# Sheet1.net
KiCad netlist of a schematic drawn in Altium Designer
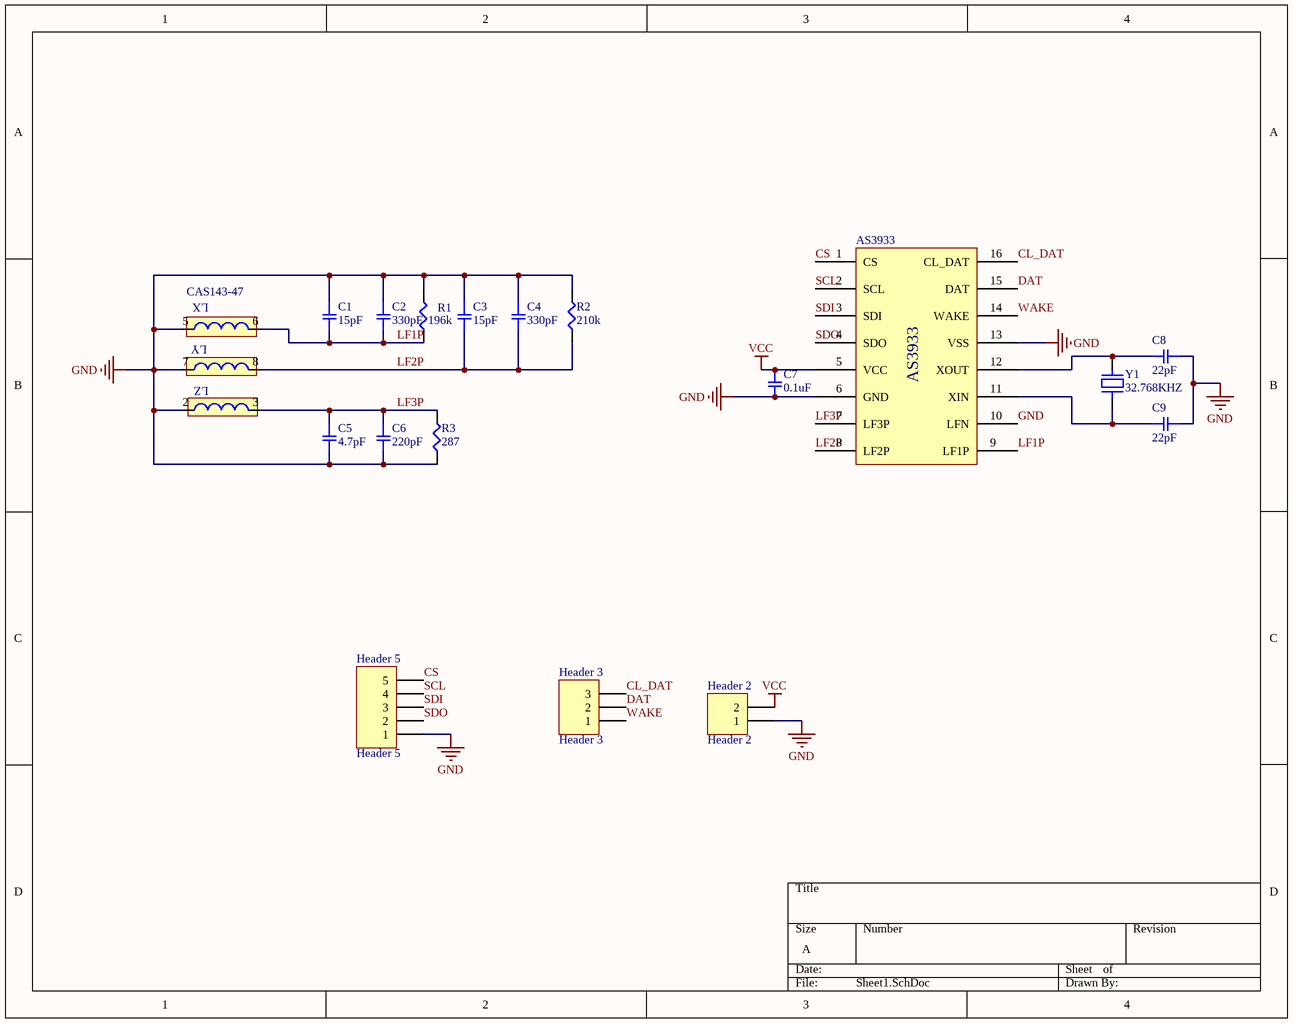
[diagram p0: Sheet1.SchDoc]

(export (version "E")
  (design (tool "Eeschema 10.0.6"))
  (components
    (comp (ref "AS3933")
      (value "~")
      (footprint "TSOP65P640X110-16N")
      (libsource (lib "AS3933") (part "Component_1"))
    )
    (comp (ref "C1")
      (value "15pF")
      (footprint "SMD-0805C")
      (description "Cap Ceramic 15pF 50V C0G 1%  0805")
      (fields (field (name "PART NUMBER") "CC0805FRNPO9BN150") (field (name "MANUFACTURER") "Yaego"))
      (libsource (lib "capacitor_0805") (part "CC0805FRNPO9BN150"))
    )
    (comp (ref "C2")
      (value "330pF")
      (footprint "SMD-0805C")
      (description "Cap Ceramic 330pF 50V C0G 2%  0805")
      (fields (field (name "PART NUMBER") "CC0805GRNPO9BN331") (field (name "MANUFACTURER") "Yageo"))
      (libsource (lib "capacitor_0805") (part "CC0805GRNPO9BN331"))
    )
    (comp (ref "C3")
      (value "15pF")
      (footprint "SMD-0805C")
      (description "Cap Ceramic 15pF 50V C0G 1%  0805")
      (fields (field (name "PART NUMBER") "CC0805FRNPO9BN150") (field (name "MANUFACTURER") "Yaego"))
      (libsource (lib "capacitor_0805") (part "CC0805FRNPO9BN150"))
    )
    (comp (ref "C4")
      (value "330pF")
      (footprint "SMD-0805C")
      (description "Cap Ceramic 330pF 50V C0G 2%  0805")
      (fields (field (name "PART NUMBER") "CC0805GRNPO9BN331") (field (name "MANUFACTURER") "Yageo"))
      (libsource (lib "capacitor_0805") (part "CC0805GRNPO9BN331"))
    )
    (comp (ref "C5")
      (value "4.7pF")
      (footprint "SMD-0805C")
      (description "Cap Ceramic 4.7pF 50V C0G 0.1pF  0805")
      (fields
        (field (name "PART NUMBER") "CL21C4R7BBANNNC")
        (field (name "MANUFACTURER") "Samsung Electro-Mechanics")
      )
      (libsource (lib "capacitor_0805") (part "CL21C4R7BBANNNC"))
    )
    (comp (ref "C6")
      (value "220pF")
      (footprint "SMD-0805C")
      (description "Cap Ceramic 220pF 100V C0G 1% 0805")
      (fields
        (field (name "PART NUMBER") "GCM2165C2A221FA16D")
        (field (name "MANUFACTURER") "Murata Manufacturing")
      )
      (libsource (lib "capacitor_0805") (part "GCM2165C2A221FA16D"))
    )
    (comp (ref "C7")
      (value "0.1uF")
      (footprint "SMD-0805C")
      (description "CAP CER 0.1uF 50V X7T 0805")
      (fields
        (field (name "PART NUMBER") "GC321AD72E103KX01D")
        (field (name "MANUFACTURER") "Samsung Electro-Mechanics")
      )
      (libsource (lib "capacitor_0805") (part "CL21B104JBCNNNC"))
    )
    (comp (ref "C8")
      (value "22pF")
      (footprint "SMD-0805C")
      (description "Cap Ceramic 22pF 50V C0G 5%0805")
      (fields
        (field (name "PART NUMBER") "CL21C220JBANNND")
        (field (name "MANUFACTURER") "Samsung Electro-Mechanics")
      )
      (libsource (lib "capacitor_0805") (part "CL21C220JBANNND"))
    )
    (comp (ref "C9")
      (value "22pF")
      (footprint "SMD-0805C")
      (description "Cap Ceramic 22pF 50V C0G 5%0805")
      (fields
        (field (name "PART NUMBER") "CL21C220JBANNND")
        (field (name "MANUFACTURER") "Samsung Electro-Mechanics")
      )
      (libsource (lib "capacitor_0805") (part "CL21C220JBANNND"))
    )
    (comp (ref "CAS143-47")
      (value "CAS143-47")
      (footprint "CAS143-47")
      (libsource (lib "CAS143-47") (part "Component_1"))
    )
    (comp (ref "Header 2")
      (value "Header 2")
      (footprint "HDR1X2")
      (description "Header, 2-Pin")
      (fields (field (name "PUBLISHER") "Altium Limited"))
      (libsource (lib "Miscellaneous Connectors") (part "Header 2"))
    )
    (comp (ref "Header 3")
      (value "Header 3")
      (footprint "HDR1X3")
      (description "Header, 3-Pin")
      (fields (field (name "PUBLISHER") "Altium Limited"))
      (libsource (lib "Miscellaneous Connectors") (part "Header 3"))
    )
    (comp (ref "Header 5")
      (value "Header 5")
      (footprint "HDR1X5")
      (description "Header, 5-Pin")
      (fields (field (name "PUBLISHER") "Altium Limited"))
      (libsource (lib "Miscellaneous Connectors") (part "Header 5"))
    )
    (comp (ref "R1")
      (value "196k")
      (footprint "SMD-0805-RES")
      (description "RES SMD 196K OHM 1% 1/8W 0805")
      (fields
        (field (name "PART NUMBER") "ERJ-6ENF1963V")
        (field (name "DIGI-KEY PART NUMBER") "P196KCCT-ND")
      )
      (libsource (lib "Panasonic_ERJ_0805") (part "ERJ-6ENF1963V"))
    )
    (comp (ref "R2")
      (value "210k")
      (footprint "SMD-0805-RES")
      (description "RES SMD 210K OHM 1% 1/8W 0805")
      (fields
        (field (name "PART NUMBER") "ERJ-6ENF2103V")
        (field (name "DIGI-KEY PART NUMBER") "P210KCCT-ND")
      )
      (libsource (lib "Panasonic_ERJ_0805") (part "ERJ-6ENF2103V"))
    )
    (comp (ref "R3")
      (value "287")
      (footprint "SMD-0805-RES")
      (description "RES SMD 287 OHM 1% 1/8W 0805")
      (fields (field (name "PART NUMBER") "ERJ-6ENF2870V") (field (name "DIGI-KEY PART NUMBER") "P287CCT-ND"))
      (libsource (lib "Panasonic_ERJ_0805") (part "ERJ-6ENF2870V"))
    )
    (comp (ref "Y1")
      (value "32.768KHZ")
      (footprint "ABRACON ABS07")
      (description "SMT Crystal")
      (libsource (lib "Crystals") (part "Abracon Crystal ABS07"))
    )
  )
  (nets
    (net (code "1") (name "/CL_DAT") (class "Default")
      (node (ref "AS3933") (pin "16") (pinfunction "CL_DAT_16") (pintype "passive"))
      (node (ref "Header 3") (pin "3") (pinfunction "3_3") (pintype "passive"))
    )
    (net (code "2") (name "/CS") (class "Default")
      (node (ref "AS3933") (pin "1") (pinfunction "CS_1") (pintype "passive"))
      (node (ref "Header 5") (pin "5") (pinfunction "5_5") (pintype "passive"))
    )
    (net (code "3") (name "/DAT") (class "Default")
      (node (ref "AS3933") (pin "15") (pinfunction "DAT_15") (pintype "passive"))
      (node (ref "Header 3") (pin "2") (pinfunction "2_2") (pintype "passive"))
    )
    (net (code "4") (name "/LF1P") (class "Default")
      (node (ref "AS3933") (pin "9") (pinfunction "LF1P_9") (pintype "passive"))
      (node (ref "C1") (pin "2") (pinfunction "2_2") (pintype "passive"))
      (node (ref "C2") (pin "2") (pinfunction "2_2") (pintype "passive"))
      (node (ref "CAS143-47") (pin "6") (pinfunction "6_6") (pintype "passive"))
      (node (ref "R1") (pin "1") (pinfunction "1_1") (pintype "passive"))
    )
    (net (code "5") (name "/LF2P") (class "Default")
      (node (ref "AS3933") (pin "8") (pinfunction "LF2P_8") (pintype "passive"))
      (node (ref "C3") (pin "2") (pinfunction "2_2") (pintype "passive"))
      (node (ref "C4") (pin "2") (pinfunction "2_2") (pintype "passive"))
      (node (ref "CAS143-47") (pin "8") (pinfunction "8_8") (pintype "passive"))
      (node (ref "R2") (pin "1") (pinfunction "1_1") (pintype "passive"))
    )
    (net (code "6") (name "/LF3P") (class "Default")
      (node (ref "AS3933") (pin "7") (pinfunction "LF3P_7") (pintype "passive"))
      (node (ref "C5") (pin "1") (pinfunction "1_1") (pintype "passive"))
      (node (ref "C6") (pin "1") (pinfunction "1_1") (pintype "passive"))
      (node (ref "CAS143-47") (pin "3") (pinfunction "3_3") (pintype "passive"))
      (node (ref "R3") (pin "2") (pinfunction "2_2") (pintype "passive"))
    )
    (net (code "7") (name "/SCL") (class "Default")
      (node (ref "AS3933") (pin "2") (pinfunction "SCL_2") (pintype "passive"))
      (node (ref "Header 5") (pin "4") (pinfunction "4_4") (pintype "passive"))
    )
    (net (code "8") (name "/SDI") (class "Default")
      (node (ref "AS3933") (pin "3") (pinfunction "SDI_3") (pintype "passive"))
      (node (ref "Header 5") (pin "3") (pinfunction "3_3") (pintype "passive"))
    )
    (net (code "9") (name "/SDO") (class "Default")
      (node (ref "AS3933") (pin "4") (pinfunction "SDO_4") (pintype "passive"))
      (node (ref "Header 5") (pin "2") (pinfunction "2_2") (pintype "passive"))
    )
    (net (code "10") (name "/WAKE") (class "Default")
      (node (ref "AS3933") (pin "14") (pinfunction "WAKE_14") (pintype "passive"))
      (node (ref "Header 3") (pin "1") (pinfunction "1_1") (pintype "passive"))
    )
    (net (code "11") (name "GND") (class "Default")
      (node (ref "AS3933") (pin "10") (pinfunction "LFN_10") (pintype "passive"))
      (node (ref "AS3933") (pin "13") (pinfunction "VSS_13") (pintype "passive"))
      (node (ref "AS3933") (pin "6") (pinfunction "GND_6") (pintype "passive"))
      (node (ref "C1") (pin "1") (pinfunction "1_1") (pintype "passive"))
      (node (ref "C2") (pin "1") (pinfunction "1_1") (pintype "passive"))
      (node (ref "C3") (pin "1") (pinfunction "1_1") (pintype "passive"))
      (node (ref "C4") (pin "1") (pinfunction "1_1") (pintype "passive"))
      (node (ref "C5") (pin "2") (pinfunction "2_2") (pintype "passive"))
      (node (ref "C6") (pin "2") (pinfunction "2_2") (pintype "passive"))
      (node (ref "C7") (pin "2") (pinfunction "2_2") (pintype "passive"))
      (node (ref "C8") (pin "1") (pinfunction "1_1") (pintype "passive"))
      (node (ref "C9") (pin "1") (pinfunction "1_1") (pintype "passive"))
      (node (ref "CAS143-47") (pin "2") (pinfunction "2_2") (pintype "passive"))
      (node (ref "CAS143-47") (pin "5") (pinfunction "5_5") (pintype "passive"))
      (node (ref "CAS143-47") (pin "7") (pinfunction "7_7") (pintype "passive"))
      (node (ref "Header 2") (pin "1") (pinfunction "1_1") (pintype "passive"))
      (node (ref "Header 5") (pin "1") (pinfunction "1_1") (pintype "passive"))
      (node (ref "R1") (pin "2") (pinfunction "2_2") (pintype "passive"))
      (node (ref "R2") (pin "2") (pinfunction "2_2") (pintype "passive"))
      (node (ref "R3") (pin "1") (pinfunction "1_1") (pintype "passive"))
    )
    (net (code "12") (name "Net-(AS3933-XIN)") (class "Default")
      (node (ref "AS3933") (pin "11") (pinfunction "XIN_11") (pintype "passive"))
      (node (ref "C9") (pin "2") (pinfunction "2_2") (pintype "passive"))
      (node (ref "Y1") (pin "1") (pinfunction "1_1") (pintype "passive"))
    )
    (net (code "13") (name "Net-(AS3933-XOUT)") (class "Default")
      (node (ref "AS3933") (pin "12") (pinfunction "XOUT_12") (pintype "passive"))
      (node (ref "C8") (pin "2") (pinfunction "2_2") (pintype "passive"))
      (node (ref "Y1") (pin "2") (pinfunction "2_2") (pintype "passive"))
    )
    (net (code "14") (name "VCC") (class "Default")
      (node (ref "AS3933") (pin "5") (pinfunction "VCC_5") (pintype "passive"))
      (node (ref "C7") (pin "1") (pinfunction "1_1") (pintype "passive"))
      (node (ref "Header 2") (pin "2") (pinfunction "2_2") (pintype "passive"))
    )
  )
)
